# Ivy_Sensor_Shield.net
KiCad netlist of a schematic drawn in EAGLE
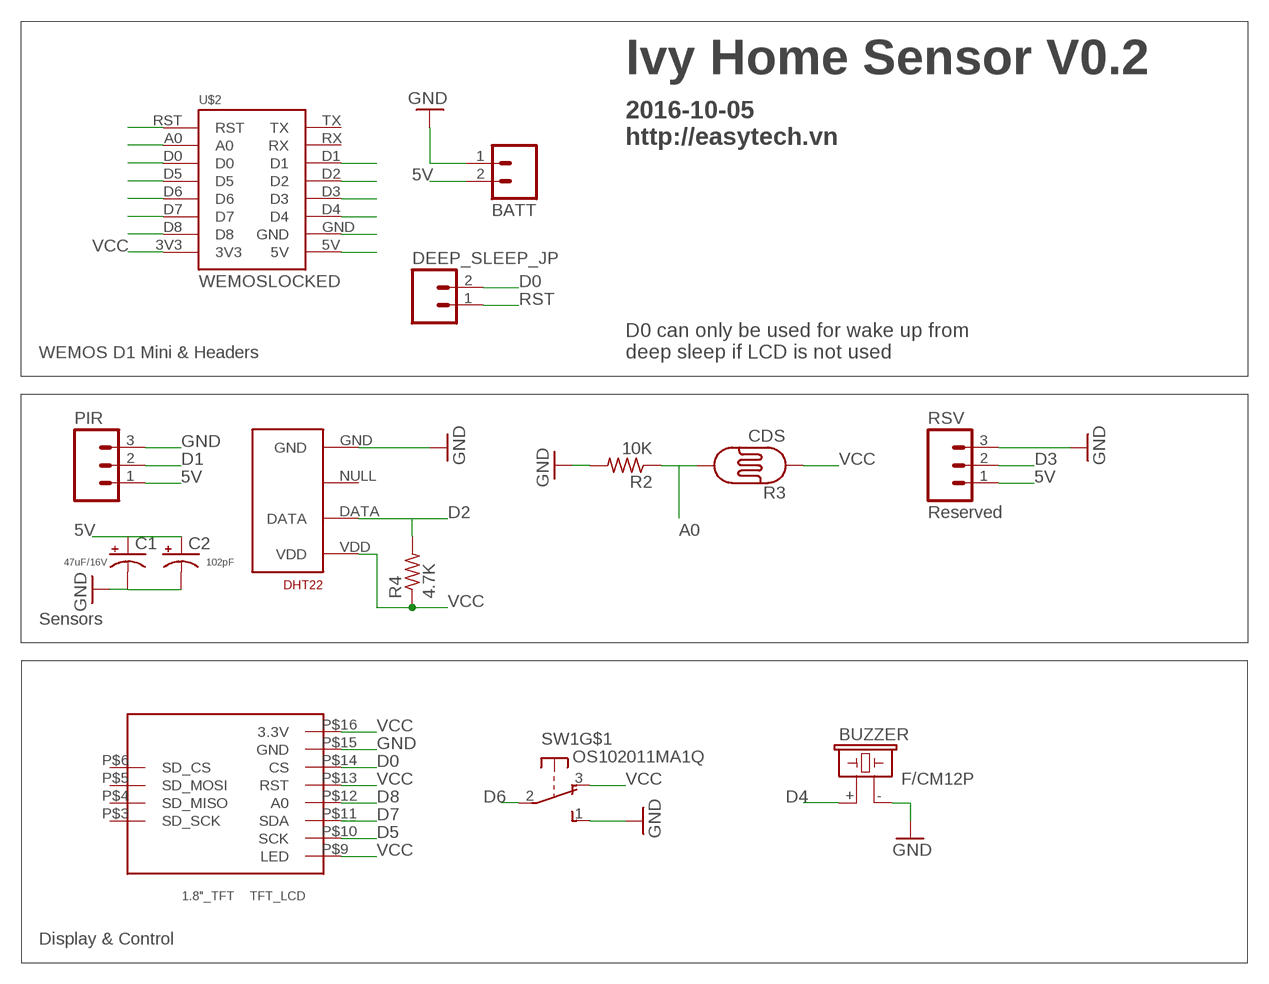
[diagram p0: schematic, sheet 1]

(export (version "E")
  (design (tool "Eeschema 10.0.6"))
  (components
    (comp (ref "BATT")
      (value "M02PTH")
      (footprint "eagle-import:1X02")
      (libsource (lib "eagle-import") (part "M02PTH"))
    )
    (comp (ref "BUZZER")
      (value "F/CM12P")
      (footprint "eagle-import:F_CM12P")
      (libsource (lib "eagle-import") (part "F/CM12P"))
    )
    (comp (ref "C1")
      (value "47uF/16V")
      (footprint "eagle-import:CPOL-RADIAL-10UF-25V")
      (libsource (lib "eagle-import") (part "CAP_POLPTH2"))
    )
    (comp (ref "C2")
      (value "102pF")
      (footprint "eagle-import:CPOL-RADIAL-10UF-25V")
      (libsource (lib "eagle-import") (part "CAP_POLPTH2"))
    )
    (comp (ref "DEEP_SLEEP_JP")
      (value "M02PTH")
      (footprint "eagle-import:1X02")
      (libsource (lib "eagle-import") (part "M02PTH"))
    )
    (comp (ref "DHT22")
      (value "RHT03_DHT-22_AM2302RA")
      (footprint "eagle-import:RHT03_DHT-22_RA")
      (libsource (lib "eagle-import") (part "RHT03_DHT-22_AM2302RA"))
    )
    (comp (ref "PIR")
      (value "M03PTH")
      (footprint "eagle-import:1X03")
      (libsource (lib "eagle-import") (part "M03PTH"))
    )
    (comp (ref "R2")
      (value "10K")
      (footprint "eagle-import:R0805")
      (libsource (lib "eagle-import") (part "R-US_R0805"))
    )
    (comp (ref "R3")
      (value "CDS")
      (footprint "eagle-import:PHOTOCELL_THIN")
      (libsource (lib "eagle-import") (part "PHOTOCELL"))
    )
    (comp (ref "R4")
      (value "4.7K")
      (footprint "eagle-import:R0805")
      (libsource (lib "eagle-import") (part "R-US_R0805"))
    )
    (comp (ref "RSV")
      (value "Reserved")
      (footprint "eagle-import:1X03")
      (libsource (lib "eagle-import") (part "M03PTH"))
    )
    (comp (ref "SW1")
      (value "OS102011MA1Q")
      (footprint "eagle-import:OS102011MA1Q")
      (libsource (lib "eagle-import") (part "OS102011MA1Q"))
    )
    (comp (ref "TFT_LCD")
      (value "1.8\"_TFT")
      (footprint "eagle-import:1.8__TFT")
      (libsource (lib "eagle-import") (part "1.8{dblquote}_TFT"))
    )
    (comp (ref "U$2")
      (value "WEMOSLOCKED")
      (footprint "eagle-import:WEMOS_LOCKED")
      (libsource (lib "eagle-import") (part "WEMOSLOCKED"))
    )
  )
  (nets
    (net (code "1") (name "/5V") (class "Default")
      (node (ref "BATT") (pin "2") (pinfunction "2_2") (pintype "passive"))
      (node (ref "C1") (pin "1") (pinfunction "+_1") (pintype "passive"))
      (node (ref "C2") (pin "1") (pinfunction "+_1") (pintype "passive"))
      (node (ref "PIR") (pin "1") (pinfunction "1_1") (pintype "passive"))
      (node (ref "RSV") (pin "1") (pinfunction "1_1") (pintype "passive"))
      (node (ref "U$2") (pin "5V") (pinfunction "5V_5V") (pintype "bidirectional"))
    )
    (net (code "2") (name "/A0") (class "Default")
      (node (ref "R2") (pin "1") (pinfunction "1_1") (pintype "passive"))
      (node (ref "R3") (pin "2") (pinfunction "P$2_2") (pintype "bidirectional"))
      (node (ref "U$2") (pin "A0") (pinfunction "A0_A0") (pintype "bidirectional"))
    )
    (net (code "3") (name "/D0") (class "Default")
      (node (ref "DEEP_SLEEP_JP") (pin "2") (pinfunction "2_2") (pintype "passive"))
      (node (ref "TFT_LCD") (pin "P$14") (pinfunction "CS_P$14") (pintype "bidirectional"))
      (node (ref "U$2") (pin "D0") (pinfunction "D0_D0") (pintype "bidirectional"))
    )
    (net (code "4") (name "/D1") (class "Default")
      (node (ref "PIR") (pin "2") (pinfunction "2_2") (pintype "passive"))
      (node (ref "U$2") (pin "D1") (pinfunction "D1_D1") (pintype "bidirectional"))
    )
    (net (code "5") (name "/D2") (class "Default")
      (node (ref "DHT22") (pin "DATA") (pinfunction "DATA_DATA") (pintype "bidirectional"))
      (node (ref "R4") (pin "2") (pinfunction "2_2") (pintype "passive"))
      (node (ref "U$2") (pin "D2") (pinfunction "D2_D2") (pintype "bidirectional"))
    )
    (net (code "6") (name "/D3") (class "Default")
      (node (ref "RSV") (pin "2") (pinfunction "2_2") (pintype "passive"))
      (node (ref "U$2") (pin "D3") (pinfunction "D3_D3") (pintype "bidirectional"))
    )
    (net (code "7") (name "/D4") (class "Default")
      (node (ref "BUZZER") (pin "+") (pinfunction "1_+") (pintype "passive"))
      (node (ref "U$2") (pin "D4") (pinfunction "D4_D4") (pintype "bidirectional"))
    )
    (net (code "8") (name "/D5") (class "Default")
      (node (ref "TFT_LCD") (pin "P$10") (pinfunction "SCK_P$10") (pintype "bidirectional"))
      (node (ref "U$2") (pin "D5") (pinfunction "D5_D5") (pintype "bidirectional"))
    )
    (net (code "9") (name "/D6") (class "Default")
      (node (ref "SW1") (pin "2") (pinfunction "P_2") (pintype "passive"))
      (node (ref "U$2") (pin "D6") (pinfunction "D6_D6") (pintype "bidirectional"))
    )
    (net (code "10") (name "/D7") (class "Default")
      (node (ref "TFT_LCD") (pin "P$11") (pinfunction "SDA_P$11") (pintype "bidirectional"))
      (node (ref "U$2") (pin "D7") (pinfunction "D7_D7") (pintype "bidirectional"))
    )
    (net (code "11") (name "/D8") (class "Default")
      (node (ref "TFT_LCD") (pin "P$12") (pinfunction "A0_P$12") (pintype "bidirectional"))
      (node (ref "U$2") (pin "D8") (pinfunction "D8_D8") (pintype "bidirectional"))
    )
    (net (code "12") (name "/RST") (class "Default")
      (node (ref "DEEP_SLEEP_JP") (pin "1") (pinfunction "1_1") (pintype "passive"))
      (node (ref "U$2") (pin "RST") (pinfunction "RST_RST") (pintype "bidirectional"))
    )
    (net (code "13") (name "/VCC") (class "Default")
      (node (ref "DHT22") (pin "VDD") (pinfunction "VDD_VDD") (pintype "power_in"))
      (node (ref "R3") (pin "1") (pinfunction "P$1_1") (pintype "bidirectional"))
      (node (ref "R4") (pin "1") (pinfunction "1_1") (pintype "passive"))
      (node (ref "SW1") (pin "3") (pinfunction "O_3") (pintype "passive"))
      (node (ref "TFT_LCD") (pin "P$13") (pinfunction "RST_P$13") (pintype "bidirectional"))
      (node (ref "TFT_LCD") (pin "P$16") (pinfunction "3.3V_P$16") (pintype "bidirectional"))
      (node (ref "TFT_LCD") (pin "P$9") (pinfunction "LED_P$9") (pintype "bidirectional"))
      (node (ref "U$2") (pin "3V3") (pinfunction "3V3_3V3") (pintype "bidirectional"))
    )
    (net (code "14") (name "GND") (class "Default")
      (node (ref "BATT") (pin "1") (pinfunction "1_1") (pintype "passive"))
      (node (ref "BUZZER") (pin "-") (pinfunction "2_-") (pintype "passive"))
      (node (ref "C1") (pin "2") (pinfunction "-_2") (pintype "passive"))
      (node (ref "C2") (pin "2") (pinfunction "-_2") (pintype "passive"))
      (node (ref "DHT22") (pin "GND") (pinfunction "GND_GND") (pintype "power_in"))
      (node (ref "PIR") (pin "3") (pinfunction "3_3") (pintype "passive"))
      (node (ref "R2") (pin "2") (pinfunction "2_2") (pintype "passive"))
      (node (ref "RSV") (pin "3") (pinfunction "3_3") (pintype "passive"))
      (node (ref "SW1") (pin "1") (pinfunction "S_1") (pintype "passive"))
      (node (ref "TFT_LCD") (pin "P$15") (pinfunction "GND_P$15") (pintype "bidirectional"))
      (node (ref "U$2") (pin "GND") (pinfunction "GND_GND") (pintype "bidirectional"))
    )
    (net (code "15") (name "unconnected-(DHT22-PadNULL)") (class "Default")
      (node (ref "DHT22") (pin "NULL") (pinfunction "NULL_NULL") (pintype "no_connect"))
    )
    (net (code "16") (name "unconnected-(TFT_LCD-SD_CS-PadP$6)") (class "Default")
      (node (ref "TFT_LCD") (pin "P$6") (pinfunction "SD_CS_P$6") (pintype "bidirectional"))
    )
    (net (code "17") (name "unconnected-(TFT_LCD-SD_MISO-PadP$4)") (class "Default")
      (node (ref "TFT_LCD") (pin "P$4") (pinfunction "SD_MISO_P$4") (pintype "bidirectional"))
    )
    (net (code "18") (name "unconnected-(TFT_LCD-SD_MOSI-PadP$5)") (class "Default")
      (node (ref "TFT_LCD") (pin "P$5") (pinfunction "SD_MOSI_P$5") (pintype "bidirectional"))
    )
    (net (code "19") (name "unconnected-(TFT_LCD-SD_SCK-PadP$3)") (class "Default")
      (node (ref "TFT_LCD") (pin "P$3") (pinfunction "SD_SCK_P$3") (pintype "bidirectional"))
    )
    (net (code "20") (name "unconnected-(U$2-PadRX)") (class "Default")
      (node (ref "U$2") (pin "RX") (pinfunction "RX_RX") (pintype "bidirectional"))
    )
    (net (code "21") (name "unconnected-(U$2-PadTX)") (class "Default")
      (node (ref "U$2") (pin "TX") (pinfunction "TX_TX") (pintype "bidirectional"))
    )
  )
)
